# digit_2.net
KiCad netlist of a schematic drawn in EAGLE
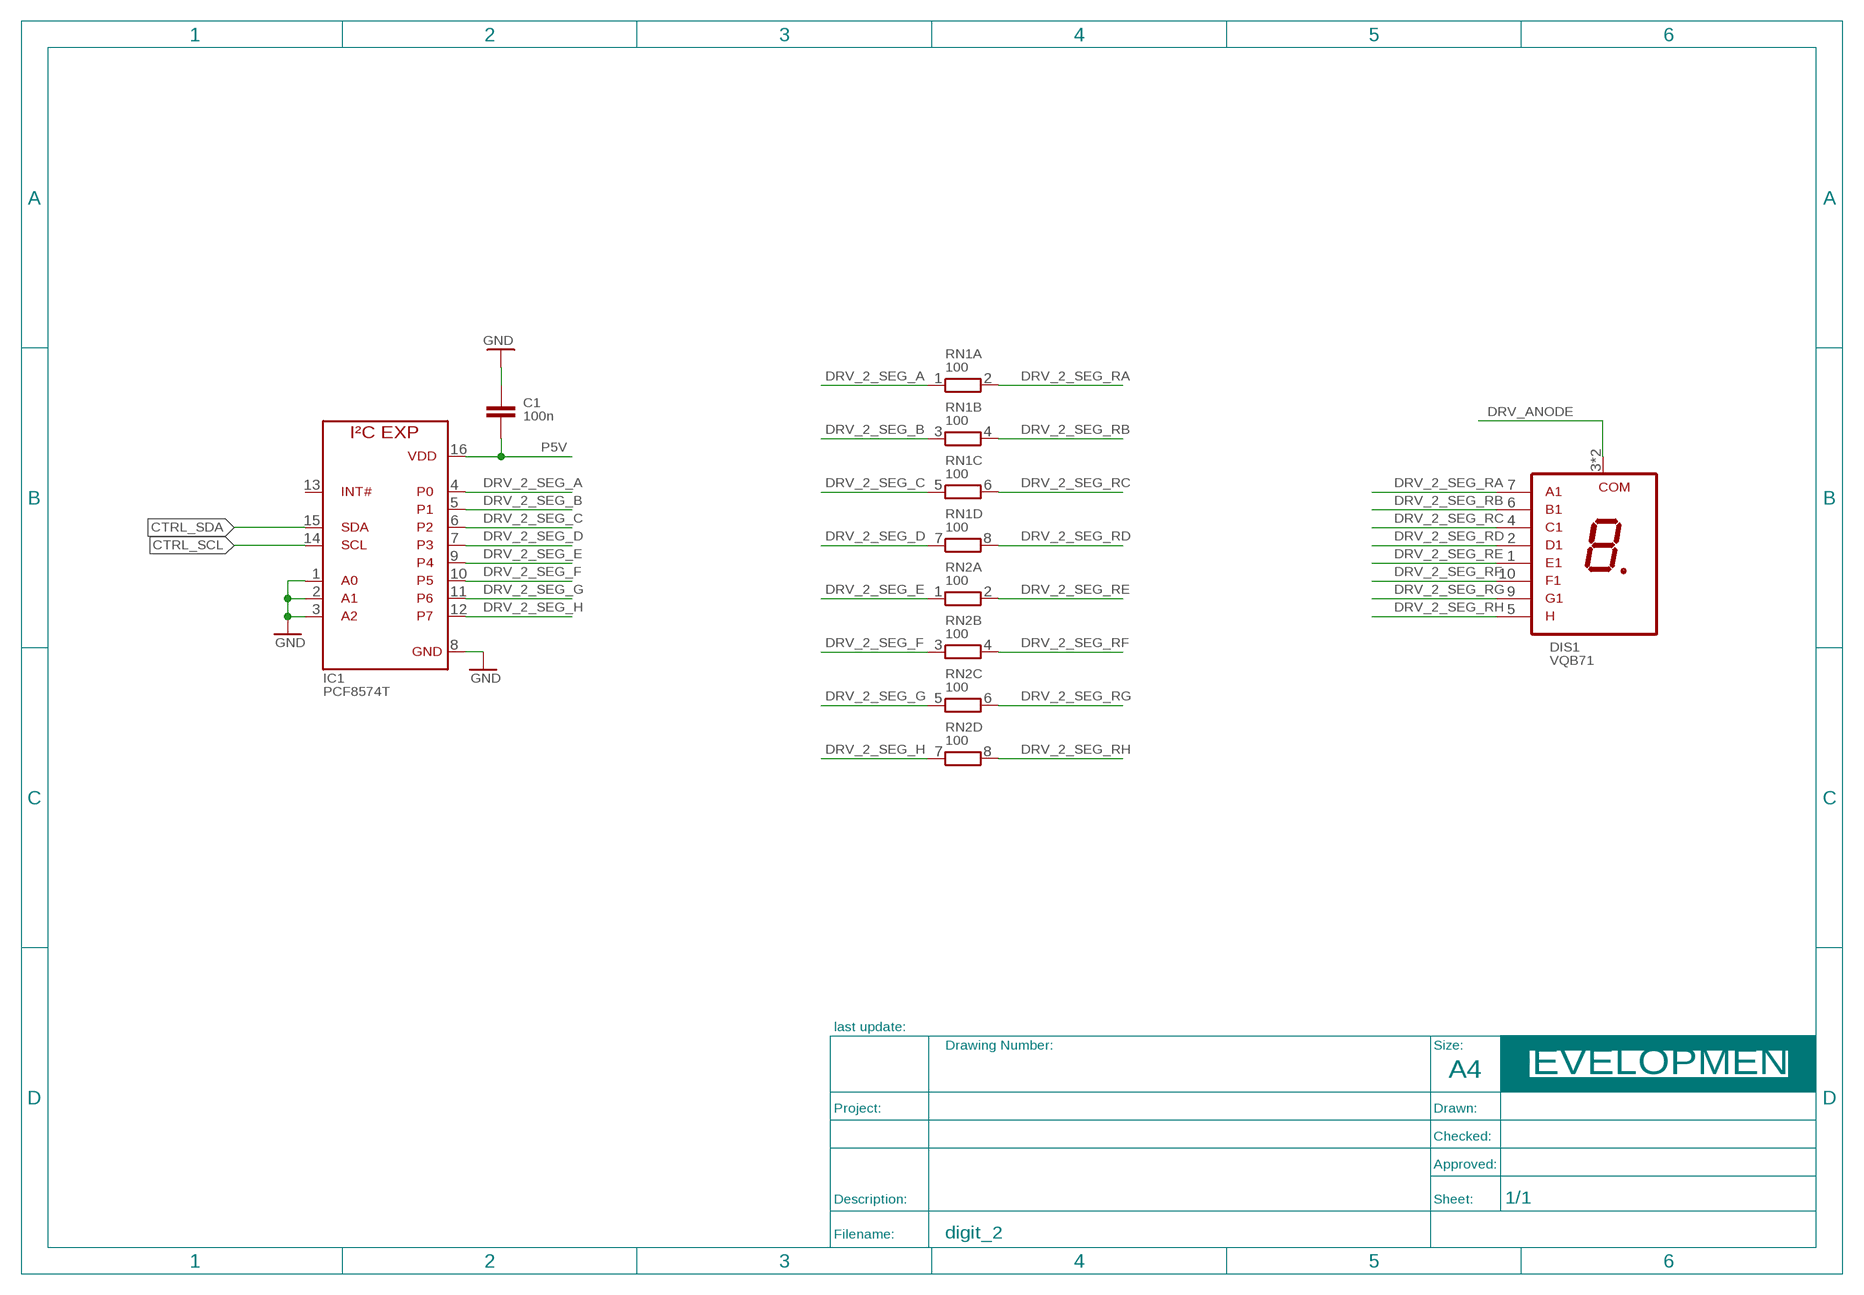
[diagram p0: schematic, sheet 1]

(export (version "E")
  (design (tool "Eeschema 10.0.6"))
  (components
    (comp (ref "C1")
      (value "100n")
      (footprint "eagle-import:S_0805")
      (fields (field (name "PART_CODE_BEL") "C_PAC_S_0805_VAL_100n"))
      (libsource (lib "eagle-import") (part "C_EU_S_0805"))
    )
    (comp (ref "DIS1")
      (value "VQB71")
      (footprint "eagle-import:T_VQB71")
      (libsource (lib "eagle-import") (part "VQB71"))
    )
    (comp (ref "IC1")
      (value "PCF8574T")
      (footprint "eagle-import:S_SOIC16")
      (libsource (lib "eagle-import") (part "PCF8574T"))
    )
    (comp (ref "RN1")
      (value "100")
      (footprint "eagle-import:T_SIL8")
      (fields (field (name "PART_CODE_BEL") "RN_PAC_T_SIL8_VAL_100"))
      (libsource (lib "eagle-import") (part "R_EU_ARRAY_4"))
    )
    (comp (ref "RN2")
      (value "100")
      (footprint "eagle-import:T_SIL8")
      (fields (field (name "PART_CODE_BEL") "RN_PAC_T_SIL8_VAL_100"))
      (libsource (lib "eagle-import") (part "R_EU_ARRAY_4"))
    )
  )
  (nets
    (net (code "1") (name "/DRV_2_SEG_A") (class "Default")
      (node (ref "IC1") (pin "4") (pinfunction "P0_4") (pintype "bidirectional"))
      (node (ref "RN1") (pin "1") (pinfunction "1_1") (pintype "passive"))
    )
    (net (code "2") (name "/DRV_2_SEG_B") (class "Default")
      (node (ref "IC1") (pin "5") (pinfunction "P1_5") (pintype "bidirectional"))
      (node (ref "RN1") (pin "3") (pinfunction "1_3") (pintype "passive"))
    )
    (net (code "3") (name "/DRV_2_SEG_C") (class "Default")
      (node (ref "IC1") (pin "6") (pinfunction "P2_6") (pintype "bidirectional"))
      (node (ref "RN1") (pin "5") (pinfunction "1_5") (pintype "passive"))
    )
    (net (code "4") (name "/DRV_2_SEG_D") (class "Default")
      (node (ref "IC1") (pin "7") (pinfunction "P3_7") (pintype "bidirectional"))
      (node (ref "RN1") (pin "7") (pinfunction "1_7") (pintype "passive"))
    )
    (net (code "5") (name "/DRV_2_SEG_E") (class "Default")
      (node (ref "IC1") (pin "9") (pinfunction "P4_9") (pintype "bidirectional"))
      (node (ref "RN2") (pin "1") (pinfunction "1_1") (pintype "passive"))
    )
    (net (code "6") (name "/DRV_2_SEG_F") (class "Default")
      (node (ref "IC1") (pin "10") (pinfunction "P5_10") (pintype "bidirectional"))
      (node (ref "RN2") (pin "3") (pinfunction "1_3") (pintype "passive"))
    )
    (net (code "7") (name "/DRV_2_SEG_G") (class "Default")
      (node (ref "IC1") (pin "11") (pinfunction "P6_11") (pintype "bidirectional"))
      (node (ref "RN2") (pin "5") (pinfunction "1_5") (pintype "passive"))
    )
    (net (code "8") (name "/DRV_2_SEG_H") (class "Default")
      (node (ref "IC1") (pin "12") (pinfunction "P7_12") (pintype "bidirectional"))
      (node (ref "RN2") (pin "7") (pinfunction "1_7") (pintype "passive"))
    )
    (net (code "9") (name "/DRV_2_SEG_RA") (class "Default")
      (node (ref "DIS1") (pin "7") (pinfunction "A1_7") (pintype "passive"))
      (node (ref "RN1") (pin "2") (pinfunction "2_2") (pintype "passive"))
    )
    (net (code "10") (name "/DRV_2_SEG_RB") (class "Default")
      (node (ref "DIS1") (pin "6") (pinfunction "B1_6") (pintype "passive"))
      (node (ref "RN1") (pin "4") (pinfunction "2_4") (pintype "passive"))
    )
    (net (code "11") (name "/DRV_2_SEG_RC") (class "Default")
      (node (ref "DIS1") (pin "4") (pinfunction "C1_4") (pintype "passive"))
      (node (ref "RN1") (pin "6") (pinfunction "2_6") (pintype "passive"))
    )
    (net (code "12") (name "/DRV_2_SEG_RD") (class "Default")
      (node (ref "DIS1") (pin "2") (pinfunction "D1_2") (pintype "passive"))
      (node (ref "RN1") (pin "8") (pinfunction "2_8") (pintype "passive"))
    )
    (net (code "13") (name "/DRV_2_SEG_RE") (class "Default")
      (node (ref "DIS1") (pin "1") (pinfunction "E1_1") (pintype "passive"))
      (node (ref "RN2") (pin "2") (pinfunction "2_2") (pintype "passive"))
    )
    (net (code "14") (name "/DRV_2_SEG_RF") (class "Default")
      (node (ref "DIS1") (pin "10") (pinfunction "F1_10") (pintype "passive"))
      (node (ref "RN2") (pin "4") (pinfunction "2_4") (pintype "passive"))
    )
    (net (code "15") (name "/DRV_2_SEG_RG") (class "Default")
      (node (ref "DIS1") (pin "9") (pinfunction "G1_9") (pintype "passive"))
      (node (ref "RN2") (pin "6") (pinfunction "2_6") (pintype "passive"))
    )
    (net (code "16") (name "/DRV_2_SEG_RH") (class "Default")
      (node (ref "DIS1") (pin "5") (pinfunction "DP1_5") (pintype "passive"))
      (node (ref "RN2") (pin "8") (pinfunction "2_8") (pintype "passive"))
    )
    (net (code "17") (name "/DRV_ANODE") (class "Default")
      (node (ref "DIS1") (pin "3") (pinfunction "COM1_3") (pintype "passive"))
      (node (ref "DIS1") (pin "8") (pinfunction "COM1_8") (pintype "passive"))
    )
    (net (code "18") (name "/P5V") (class "Default")
      (node (ref "C1") (pin "2") (pinfunction "2_2") (pintype "passive"))
      (node (ref "IC1") (pin "16") (pinfunction "VDD_16") (pintype "power_in"))
    )
    (net (code "19") (name "CTRL_SCL") (class "Default")
      (node (ref "IC1") (pin "14") (pinfunction "SCL_14") (pintype "input"))
    )
    (net (code "20") (name "CTRL_SDA") (class "Default")
      (node (ref "IC1") (pin "15") (pinfunction "SDA_15") (pintype "bidirectional"))
    )
    (net (code "21") (name "GND") (class "Default")
      (node (ref "C1") (pin "1") (pinfunction "1_1") (pintype "passive"))
      (node (ref "IC1") (pin "1") (pinfunction "A0_1") (pintype "input"))
      (node (ref "IC1") (pin "2") (pinfunction "A1_2") (pintype "input"))
      (node (ref "IC1") (pin "3") (pinfunction "A2_3") (pintype "input"))
      (node (ref "IC1") (pin "8") (pinfunction "GND_8") (pintype "power_in"))
    )
    (net (code "22") (name "unconnected-(IC1-~{INT}-Pad13)") (class "Default")
      (node (ref "IC1") (pin "13") (pinfunction "~{INT}_13") (pintype "output"))
    )
  )
)
